# E17-PDU-CONNECTORS.net
KiCad netlist of a schematic drawn in Altium Designer
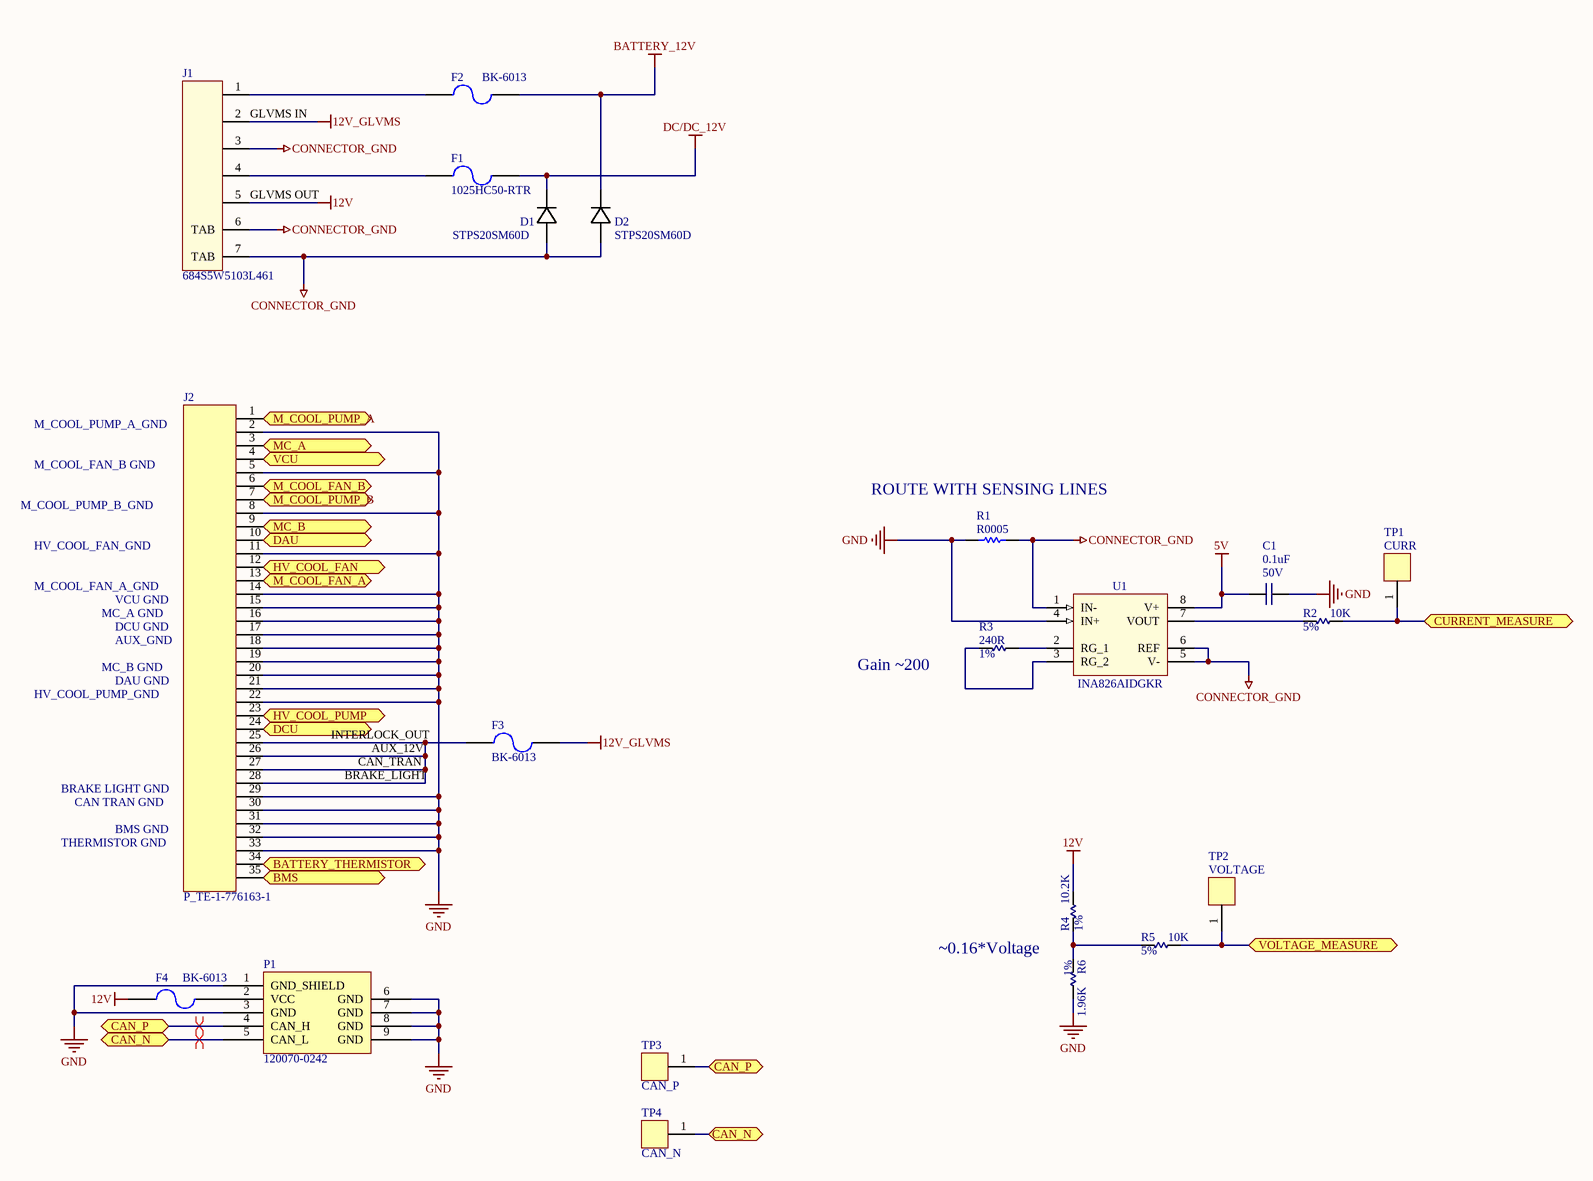
[diagram p0: E17-PDU-CONNECTORS.SchDoc]

(export (version "E")
  (design (tool "Eeschema 10.0.6"))
  (components
    (comp (ref "C1")
      (value "0.1uF")
      (footprint "C0805")
      (description "Generic 0805 Capacitor")
      (fields
        (field (name "TOLERANCE") "10%")
        (field (name "VOLTAGE") "50V")
        (field (name "Comment") "C_0805_Generic")
      )
      (libsource (lib "Compiled_PDU") (part "C_0805_Generic"))
    )
    (comp (ref "D1")
      (value "D_STPS20SM60D")
      (footprint "TO-220-2")
      (description "DIODE 630mV 20A cts 60V")
      (fields (field (name "MFG") "ST") (field (name "MFG_PN") "STPS20SM60D"))
      (libsource (lib "Compiled_PDU") (part "D_STPS20SM60D"))
    )
    (comp (ref "D2")
      (value "D_STPS20SM60D")
      (footprint "TO-220-2")
      (description "DIODE 630mV 20A cts 60V")
      (fields (field (name "MFG") "ST") (field (name "MFG_PN") "STPS20SM60D"))
      (libsource (lib "Compiled_PDU") (part "D_STPS20SM60D"))
    )
    (comp (ref "F1")
      (value "F_1025HC50-RTR")
      (footprint "F_1025HC50-RTR")
      (description "FUSE 50A 60VDC")
      (fields (field (name "MFG") "Eaton") (field (name "MFG_PN") "1025HC50-RTR"))
      (libsource (lib "Compiled_PDU") (part "F_1025HC50-RTR"))
    )
    (comp (ref "F2")
      (value "F_BK-6013")
      (footprint "BK-6013")
      (description "FUSE HOLDER BLADE PCB")
      (fields (field (name "MFG") "MPD") (field (name "MFG_PN") "BK-6013"))
      (libsource (lib "Compiled_PDU") (part "F_BK-6013"))
    )
    (comp (ref "F3")
      (value "F_BK-6013")
      (footprint "BK-6013")
      (description "FUSE HOLDER BLADE PCB")
      (fields (field (name "MFG") "MPD") (field (name "MFG_PN") "BK-6013"))
      (libsource (lib "Compiled_PDU") (part "F_BK-6013"))
    )
    (comp (ref "F4")
      (value "F_BK-6013")
      (footprint "BK-6013")
      (description "FUSE HOLDER BLADE PCB")
      (fields (field (name "MFG") "MPD") (field (name "MFG_PN") "BK-6013"))
      (libsource (lib "Compiled_PDU") (part "F_BK-6013"))
    )
    (comp (ref "J1")
      (value "J_684S5W5103L461")
      (footprint "J_684S5W5103L461")
      (description "D-Sub 5-pin 40A RA TH")
      (fields (field (name "MFG") "NorComp") (field (name "MFG_PN") "684S5W5103L461"))
      (libsource (lib "Compiled_PDU") (part "J_684S5W5103L461"))
    )
    (comp (ref "J2")
      (value "P_TE-1-776163-1")
      (footprint "P_TE-1-776163-1")
      (description "CONN HEADER 35POS R/A GOLD BLACK")
      (fields (field (name "MFG") "TE"))
      (libsource (lib "Compiled_PDU") (part "P_TE-1-776163-1"))
    )
    (comp (ref "P1")
      (value "P_CAN-CONNECTOR")
      (footprint "CAN Connector (90)")
      (fields (field (name "MFG") "MOLEX") (field (name "MFG_PN") "120070-0242"))
      (libsource (lib "Compiled_PDU") (part "P_CAN-CONNECTOR"))
    )
    (comp (ref "R1")
      (value "R0005")
      (footprint "PSR500HTQFC0L20")
      (description "Resistor 0.0002ohm 5W Current Sense")
      (fields (field (name "MFG") "Rohm") (field (name "Comment") "R_PSR500HTQFC0L20"))
      (libsource (lib "Compiled_PDU") (part "R_PSR500HTQFC0L20"))
    )
    (comp (ref "R2")
      (value "10K")
      (footprint "R0805")
      (description "Generic 0805 Resistor")
      (fields
        (field (name "POWER") "1/8W")
        (field (name "TOLERANCE") "5%")
        (field (name "Comment") "R_0805_Generic")
      )
      (libsource (lib "Compiled_PDU") (part "R_0805_Generic"))
    )
    (comp (ref "R3")
      (value "240R")
      (footprint "R0805")
      (description "Generic 0805 Resistor")
      (fields
        (field (name "POWER") "1/8W")
        (field (name "TOLERANCE") "1%")
        (field (name "Comment") "R_0805_Generic")
      )
      (libsource (lib "Compiled_PDU") (part "R_0805_Generic"))
    )
    (comp (ref "R4")
      (value "10.2K")
      (footprint "R0805")
      (description "Generic 0805 Resistor")
      (fields
        (field (name "POWER") "1/8W")
        (field (name "TOLERANCE") "1%")
        (field (name "Comment") "R_0805_Generic")
      )
      (libsource (lib "Compiled_PDU") (part "R_0805_Generic"))
    )
    (comp (ref "R5")
      (value "10K")
      (footprint "R0805")
      (description "Generic 0805 Resistor")
      (fields
        (field (name "POWER") "1/8W")
        (field (name "TOLERANCE") "5%")
        (field (name "Comment") "R_0805_Generic")
      )
      (libsource (lib "Compiled_PDU") (part "R_0805_Generic"))
    )
    (comp (ref "R6")
      (value "1.96K")
      (footprint "R0805")
      (description "Generic 0805 Resistor")
      (fields
        (field (name "POWER") "1/8W")
        (field (name "TOLERANCE") "1%")
        (field (name "Comment") "R_0805_Generic")
      )
      (libsource (lib "Compiled_PDU") (part "R_0805_Generic"))
    )
    (comp (ref "TP1")
      (value "CURR")
      (footprint "TEST POINT")
      (description "Test Point")
      (libsource (lib "") (part "Test Point_1"))
    )
    (comp (ref "TP2")
      (value "VOLTAGE")
      (footprint "TEST POINT")
      (description "Test Point")
      (libsource (lib "") (part "Test Point_1"))
    )
    (comp (ref "TP3")
      (value "CAN_P")
      (footprint "TEST POINT")
      (description "Test Point")
      (libsource (lib "Compiled_PDU") (part "Test Point"))
    )
    (comp (ref "TP4")
      (value "CAN_N")
      (footprint "TEST POINT")
      (description "Test Point")
      (libsource (lib "Compiled_PDU") (part "Test Point"))
    )
    (comp (ref "U1")
      (value "INA826AIDGKR")
      (footprint "8-TSSOP")
      (description "Opamp Instrumentation 2.7-36V SS")
      (fields (field (name "MFG") "TI") (field (name "Comment") "U_INA826AIDGKR"))
      (libsource (lib "Compiled_PDU") (part "U_INA826AIDGKR"))
    )
  )
  (nets
    (net (code "1") (name "/BATTERY_THERMISTOR") (class "Default")
      (node (ref "J2") (pin "34") (pintype "passive"))
    )
    (net (code "2") (name "/BMS") (class "Default") (node (ref "J2") (pin "35") (pintype "passive")))
    (net (code "3") (name "/CAN_N") (class "Default")
      (node (ref "P1") (pin "5") (pinfunction "CAN_L_5") (pintype "passive"))
      (node (ref "TP4") (pin "1") (pintype "passive"))
    )
    (net (code "4") (name "/CAN_P") (class "Default")
      (node (ref "P1") (pin "4") (pinfunction "CAN_H_4") (pintype "passive"))
      (node (ref "TP3") (pin "1") (pintype "passive"))
    )
    (net (code "5") (name "/CURRENT_MEASURE") (class "Default")
      (node (ref "R2") (pin "2") (pinfunction "2_2") (pintype "passive"))
      (node (ref "TP1") (pin "1") (pintype "passive"))
    )
    (net (code "6") (name "/DAU") (class "Default") (node (ref "J2") (pin "10") (pintype "passive")))
    (net (code "7") (name "/DCU") (class "Default") (node (ref "J2") (pin "24") (pintype "passive")))
    (net (code "8") (name "/HV_COOL_FAN") (class "Default") (node (ref "J2") (pin "12") (pintype "passive")))
    (net (code "9") (name "/HV_COOL_PUMP") (class "Default") (node (ref "J2") (pin "23") (pintype "passive")))
    (net (code "10") (name "/MC_A") (class "Default") (node (ref "J2") (pin "3") (pintype "passive")))
    (net (code "11") (name "/MC_B") (class "Default") (node (ref "J2") (pin "9") (pintype "passive")))
    (net (code "12") (name "/M_COOL_FAN_A") (class "Default")
      (node (ref "J2") (pin "13") (pintype "passive"))
    )
    (net (code "13") (name "/M_COOL_FAN_B") (class "Default") (node (ref "J2") (pin "6") (pintype "passive")))
    (net (code "14") (name "/M_COOL_PUMP_A") (class "Default")
      (node (ref "J2") (pin "1") (pintype "passive"))
    )
    (net (code "15") (name "/M_COOL_PUMP_B") (class "Default")
      (node (ref "J2") (pin "7") (pintype "passive"))
    )
    (net (code "16") (name "/VCU") (class "Default") (node (ref "J2") (pin "4") (pintype "passive")))
    (net (code "17") (name "/VOLTAGE_MEASURE") (class "Default")
      (node (ref "R5") (pin "2") (pinfunction "2_2") (pintype "passive"))
      (node (ref "TP2") (pin "1") (pintype "passive"))
    )
    (net (code "18") (name "5V") (class "Default")
      (node (ref "C1") (pin "2") (pinfunction "2_2") (pintype "passive"))
      (node (ref "U1") (pin "8") (pinfunction "V+_8") (pintype "power_in"))
    )
    (net (code "19") (name "12V") (class "Default")
      (node (ref "F4") (pin "2") (pinfunction "2_2") (pintype "passive"))
      (node (ref "J1") (pin "5") (pinfunction "5_5") (pintype "passive"))
      (node (ref "R4") (pin "2") (pinfunction "2_2") (pintype "passive"))
    )
    (net (code "20") (name "12V_GLVMS") (class "Default")
      (node (ref "F3") (pin "2") (pinfunction "2_2") (pintype "passive"))
      (node (ref "J1") (pin "2") (pinfunction "2_2") (pintype "passive"))
    )
    (net (code "21") (name "BATTERY_12V") (class "Default")
      (node (ref "D2") (pin "2") (pintype "passive"))
      (node (ref "F2") (pin "2") (pinfunction "2_2") (pintype "passive"))
    )
    (net (code "22") (name "CONNECTOR_GND") (class "Default")
      (node (ref "D1") (pin "1") (pintype "passive"))
      (node (ref "D2") (pin "1") (pintype "passive"))
      (node (ref "J1") (pin "3") (pinfunction "3_3") (pintype "passive"))
      (node (ref "J1") (pin "6") (pinfunction "TAB_6") (pintype "passive"))
      (node (ref "J1") (pin "7") (pinfunction "TAB_7") (pintype "passive"))
      (node (ref "R1") (pin "2") (pinfunction "2_2") (pintype "passive"))
      (node (ref "U1") (pin "1") (pinfunction "IN-_1") (pintype "input"))
      (node (ref "U1") (pin "5") (pinfunction "V-_5") (pintype "power_in"))
      (node (ref "U1") (pin "6") (pinfunction "REF_6") (pintype "power_in"))
    )
    (net (code "23") (name "DC{slash}DC_12V") (class "Default")
      (node (ref "D1") (pin "2") (pintype "passive"))
      (node (ref "F1") (pin "2") (pinfunction "2_2") (pintype "passive"))
    )
    (net (code "24") (name "GND") (class "Default")
      (node (ref "C1") (pin "1") (pinfunction "EGND_1") (pintype "passive"))
      (node (ref "J2") (pin "11") (pintype "passive"))
      (node (ref "J2") (pin "14") (pintype "passive"))
      (node (ref "J2") (pin "15") (pintype "passive"))
      (node (ref "J2") (pin "16") (pintype "passive"))
      (node (ref "J2") (pin "17") (pintype "passive"))
      (node (ref "J2") (pin "18") (pintype "passive"))
      (node (ref "J2") (pin "19") (pintype "passive"))
      (node (ref "J2") (pin "2") (pintype "passive"))
      (node (ref "J2") (pin "20") (pintype "passive"))
      (node (ref "J2") (pin "21") (pintype "passive"))
      (node (ref "J2") (pin "22") (pintype "passive"))
      (node (ref "J2") (pin "29") (pintype "passive"))
      (node (ref "J2") (pin "30") (pintype "passive"))
      (node (ref "J2") (pin "31") (pintype "passive"))
      (node (ref "J2") (pin "32") (pintype "passive"))
      (node (ref "J2") (pin "33") (pintype "passive"))
      (node (ref "J2") (pin "5") (pintype "passive"))
      (node (ref "J2") (pin "8") (pintype "passive"))
      (node (ref "P1") (pin "1") (pinfunction "GND_SHIELD_1") (pintype "passive"))
      (node (ref "P1") (pin "3") (pinfunction "GND_3") (pintype "passive"))
      (node (ref "P1") (pin "6") (pinfunction "GND_6") (pintype "passive"))
      (node (ref "P1") (pin "7") (pinfunction "GND_7") (pintype "passive"))
      (node (ref "P1") (pin "8") (pinfunction "GND_8") (pintype "passive"))
      (node (ref "P1") (pin "9") (pinfunction "GND_9") (pintype "passive"))
      (node (ref "R1") (pin "1") (pinfunction "1_1") (pintype "passive"))
      (node (ref "R6") (pin "2") (pinfunction "2_2") (pintype "passive"))
      (node (ref "U1") (pin "4") (pinfunction "IN+_4") (pintype "input"))
    )
    (net (code "25") (name "Net-(F1-Pad1)") (class "Default")
      (node (ref "F1") (pin "1") (pinfunction "1_1") (pintype "passive"))
      (node (ref "J1") (pin "4") (pinfunction "4_4") (pintype "passive"))
    )
    (net (code "26") (name "Net-(F2-Pad1)") (class "Default")
      (node (ref "F2") (pin "1") (pinfunction "1_1") (pintype "passive"))
      (node (ref "J1") (pin "1") (pinfunction "1_1") (pintype "passive"))
    )
    (net (code "27") (name "Net-(F3-Pad1)") (class "Default")
      (node (ref "F3") (pin "1") (pinfunction "1_1") (pintype "passive"))
      (node (ref "J2") (pin "25") (pintype "passive"))
      (node (ref "J2") (pin "26") (pintype "passive"))
      (node (ref "J2") (pin "27") (pintype "passive"))
      (node (ref "J2") (pin "28") (pintype "passive"))
    )
    (net (code "28") (name "Net-(P1-VCC)") (class "Default")
      (node (ref "F4") (pin "1") (pinfunction "1_1") (pintype "passive"))
      (node (ref "P1") (pin "2") (pinfunction "VCC_2") (pintype "passive"))
    )
    (net (code "29") (name "Net-(R4-Pad1)") (class "Default")
      (node (ref "R4") (pin "1") (pinfunction "1_1") (pintype "passive"))
      (node (ref "R5") (pin "1") (pinfunction "1_1") (pintype "passive"))
      (node (ref "R6") (pin "1") (pinfunction "1_1") (pintype "passive"))
    )
    (net (code "30") (name "Net-(U1-RG_1)") (class "Default")
      (node (ref "R3") (pin "2") (pinfunction "2_2") (pintype "passive"))
      (node (ref "U1") (pin "2") (pinfunction "RG_1_2") (pintype "passive"))
    )
    (net (code "31") (name "Net-(U1-RG_2)") (class "Default")
      (node (ref "R3") (pin "1") (pinfunction "1_1") (pintype "passive"))
      (node (ref "U1") (pin "3") (pinfunction "RG_2_3") (pintype "passive"))
    )
    (net (code "32") (name "Net-(U1-VOUT)") (class "Default")
      (node (ref "R2") (pin "1") (pinfunction "1_1") (pintype "passive"))
      (node (ref "U1") (pin "7") (pinfunction "VOUT_7") (pintype "power_in"))
    )
  )
)
